# Manan_final_schematic.net
KiCad netlist of a schematic drawn in EAGLE
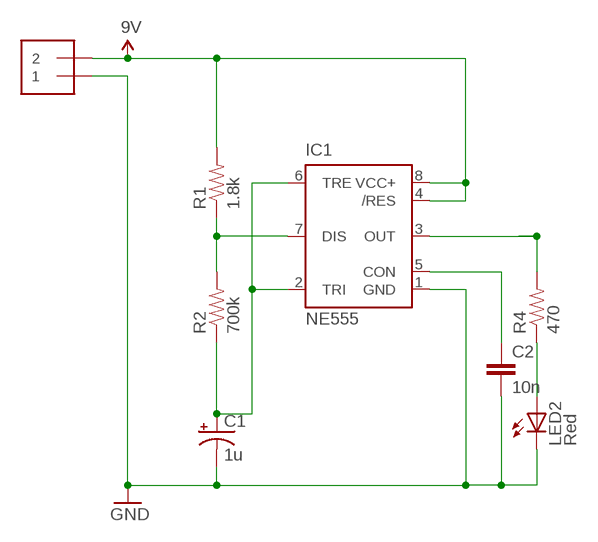
[diagram p0: schematic, sheet 1]

(export (version "E")
  (design (tool "Eeschema 10.0.6"))
  (components
    (comp (ref "C1")
      (value "1u")
      (footprint "eagle-import:CPOL-RADIAL-10UF-25V")
      (libsource (lib "eagle-import") (part "CAP_POLPTH2"))
    )
    (comp (ref "C2")
      (value "10n")
      (footprint "eagle-import:CAP-PTH-SMALL")
      (libsource (lib "eagle-import") (part "CAPPTH"))
    )
    (comp (ref "IC1")
      (value "NE555")
      (footprint "eagle-import:DIL-08")
      (fields (field (name "MF") "Arrow Electronics") (field (name "MPN") "NE555N"))
      (libsource (lib "eagle-import") (part "NE555"))
    )
    (comp (ref "J1")
      (value "1X2-3.5MM")
      (footprint "eagle-import:1X2-3.5MM")
      (libsource (lib "eagle-import") (part "1X2-3.5MM"))
    )
    (comp (ref "LED2")
      (value "Red")
      (footprint "eagle-import:LED5MM")
      (libsource (lib "eagle-import") (part "LED5MM"))
    )
    (comp (ref "R1")
      (value "1.8k")
      (footprint "eagle-import:AXIAL-0.3")
      (libsource (lib "eagle-import") (part "RESISTORAXIAL-0.3"))
    )
    (comp (ref "R2")
      (value "700k")
      (footprint "eagle-import:AXIAL-0.3")
      (libsource (lib "eagle-import") (part "RESISTORAXIAL-0.3"))
    )
    (comp (ref "R4")
      (value "470")
      (footprint "eagle-import:AXIAL-0.3")
      (libsource (lib "eagle-import") (part "RESISTORAXIAL-0.3"))
    )
  )
  (nets
    (net (code "1") (name "9V") (class "Default")
      (node (ref "IC1") (pin "4") (pinfunction "/RES_4") (pintype "input"))
      (node (ref "IC1") (pin "8") (pinfunction "VCC+_8") (pintype "power_in"))
      (node (ref "J1") (pin "2") (pinfunction "2_2") (pintype "passive"))
      (node (ref "R1") (pin "P$2") (pinfunction "2_P$2") (pintype "passive"))
    )
    (net (code "2") (name "GND") (class "Default")
      (node (ref "C1") (pin "2") (pinfunction "-_2") (pintype "passive"))
      (node (ref "C2") (pin "2") (pinfunction "2_2") (pintype "passive"))
      (node (ref "IC1") (pin "1") (pinfunction "GND_1") (pintype "power_in"))
      (node (ref "J1") (pin "1") (pinfunction "1_1") (pintype "passive"))
      (node (ref "LED2") (pin "K") (pinfunction "C_K") (pintype "passive"))
    )
    (net (code "3") (name "Net-(C1-+)") (class "Default")
      (node (ref "C1") (pin "1") (pinfunction "+_1") (pintype "passive"))
      (node (ref "IC1") (pin "2") (pinfunction "TRI_2") (pintype "input"))
      (node (ref "IC1") (pin "6") (pinfunction "TRE_6") (pintype "input"))
      (node (ref "R2") (pin "P$1") (pinfunction "1_P$1") (pintype "passive"))
    )
    (net (code "4") (name "Net-(IC1-CON)") (class "Default")
      (node (ref "C2") (pin "1") (pinfunction "1_1") (pintype "passive"))
      (node (ref "IC1") (pin "5") (pinfunction "CON_5") (pintype "input"))
    )
    (net (code "5") (name "Net-(IC1-DIS)") (class "Default")
      (node (ref "IC1") (pin "7") (pinfunction "DIS_7") (pintype "input"))
      (node (ref "R1") (pin "P$1") (pinfunction "1_P$1") (pintype "passive"))
      (node (ref "R2") (pin "P$2") (pinfunction "2_P$2") (pintype "passive"))
    )
    (net (code "6") (name "Net-(IC1-OUT)") (class "Default")
      (node (ref "IC1") (pin "3") (pinfunction "OUT_3") (pintype "output"))
      (node (ref "R4") (pin "P$2") (pinfunction "2_P$2") (pintype "passive"))
    )
    (net (code "7") (name "Net-(R4-1)") (class "Default")
      (node (ref "LED2") (pin "A") (pinfunction "A_A") (pintype "passive"))
      (node (ref "R4") (pin "P$1") (pinfunction "1_P$1") (pintype "passive"))
    )
  )
)
